# msp430.net
KiCad netlist of a schematic drawn in Altium Designer
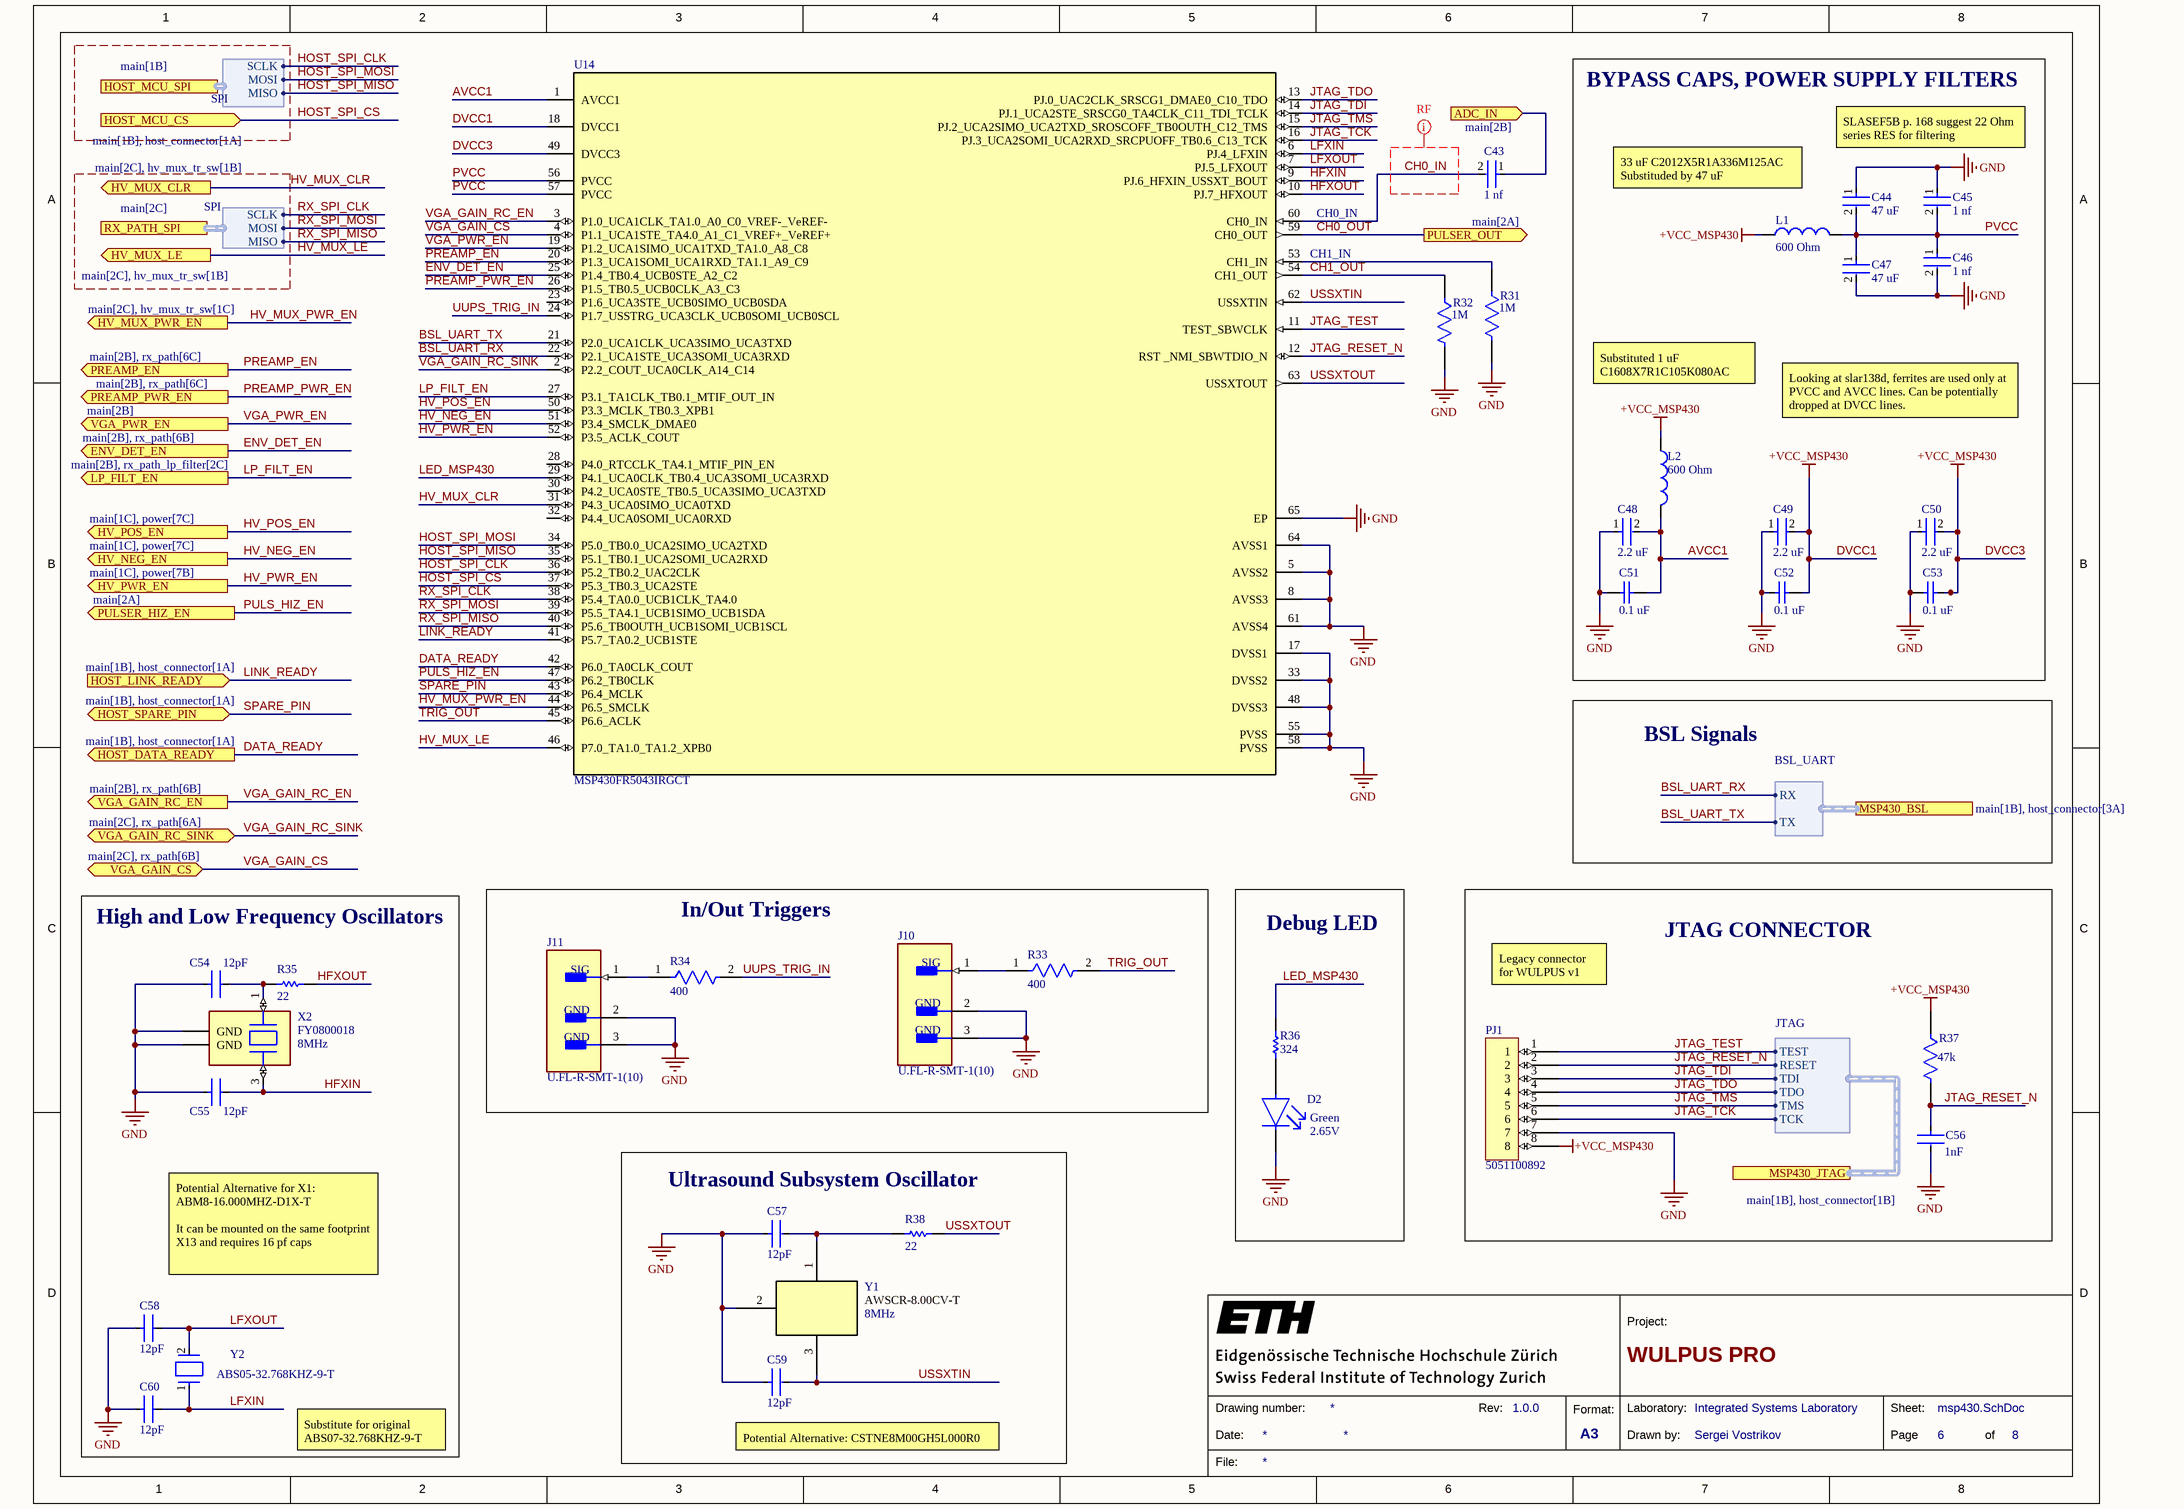
[diagram p0: msp430.SchDoc]

(export (version "E")
  (design (tool "Eeschema 10.0.6"))
  (components
    (comp (ref "C43")
      (value "1 nf")
      (footprint "FP-GRM155-0_05-IPC_B")
      (description "GRM1555C1H102JA01D")
      (fields (field (name "TOLERANCE") "5%") (field (name "VOLTAGE") "50V"))
      (libsource (lib "") (part "02cd4be3c70576c341d710602a673aa_1"))
    )
    (comp (ref "C44")
      (value "47 uF")
      (footprint "FP-GRM188-0_2-MFG")
      (description "GRM188R60J476ME01D")
      (fields (field (name "TOLERANCE") "20%"))
      (libsource (lib "Altium Content Vault") (part "b4654b650e69147ec39a6b967a45e02"))
    )
    (comp (ref "C45")
      (value "1 nf")
      (footprint "FP-GRM155-0_05-IPC_B")
      (description "GRM1555C1H102JA01D")
      (fields (field (name "TOLERANCE") "5%") (field (name "VOLTAGE") "50V"))
      (libsource (lib "") (part "02cd4be3c70576c341d710602a673aa_1"))
    )
    (comp (ref "C46")
      (value "1 nf")
      (footprint "FP-GRM155-0_05-IPC_B")
      (description "GRM1555C1H102JA01D")
      (fields (field (name "TOLERANCE") "5%") (field (name "VOLTAGE") "50V"))
      (libsource (lib "") (part "02cd4be3c70576c341d710602a673aa_1"))
    )
    (comp (ref "C47")
      (value "47 uF")
      (footprint "FP-GRM188-0_2-MFG")
      (description "GRM188R60J476ME01D")
      (fields (field (name "TOLERANCE") "20%"))
      (libsource (lib "Altium Content Vault") (part "b4654b650e69147ec39a6b967a45e02"))
    )
    (comp (ref "C48")
      (value "2.2 uF")
      (footprint "FP-C1005-050-0_15-0_1-MFG")
      (description "C1005X7S1A225K050BC")
      (fields (field (name "TOLERANCE") "10%"))
      (libsource (lib "Altium Content Vault") (part "b4654b650e69147ec39a6b967a45e02"))
    )
    (comp (ref "C49")
      (value "2.2 uF")
      (footprint "FP-C1005-050-0_15-0_1-MFG")
      (description "C1005X7S1A225K050BC")
      (fields (field (name "TOLERANCE") "10%"))
      (libsource (lib "Altium Content Vault") (part "b4654b650e69147ec39a6b967a45e02"))
    )
    (comp (ref "C50")
      (value "2.2 uF")
      (footprint "FP-C1005-050-0_15-0_1-MFG")
      (description "C1005X7S1A225K050BC")
      (fields (field (name "TOLERANCE") "10%"))
      (libsource (lib "Altium Content Vault") (part "b4654b650e69147ec39a6b967a45e02"))
    )
    (comp (ref "C51")
      (value "0.1 uF")
      (footprint "CAPC1005X55X30LL05T10")
      (description "C0402C104K4RACTU")
      (fields (field (name "MANUFACTURER") "Kemet"))
      (libsource (lib "Altium Content Vault") (part "CAP"))
    )
    (comp (ref "C52")
      (value "0.1 uF")
      (footprint "CAPC1005X55X30LL05T10")
      (description "C0402C104K4RACTU")
      (fields (field (name "MANUFACTURER") "Kemet"))
      (libsource (lib "Altium Content Vault") (part "CAP"))
    )
    (comp (ref "C53")
      (value "0.1 uF")
      (footprint "CAPC1005X55X30LL05T10")
      (description "C0402C104K4RACTU")
      (fields (field (name "MANUFACTURER") "Kemet"))
      (libsource (lib "Altium Content Vault") (part "CAP"))
    )
    (comp (ref "C54")
      (value "GJM1555C1H120GB01D")
      (footprint "FP-GJM155-0_05-IPC_A")
      (description "Multi-Layer Ceramic Capacitor 12pF C0G  ±2% 0402 Paper T/R")
      (fields (field (name "TOLERANCE") "2%") (field (name "CAPACITANCE") "12pF"))
      (libsource (lib "Altium Content Vault") (part "02cd4be3c70576c341d710602a673aa"))
    )
    (comp (ref "C55")
      (value "GJM1555C1H120GB01D")
      (footprint "FP-GJM155-0_05-IPC_A")
      (description "Multi-Layer Ceramic Capacitor 12pF C0G  ±2% 0402 Paper T/R")
      (fields (field (name "TOLERANCE") "2%") (field (name "CAPACITANCE") "12pF"))
      (libsource (lib "Altium Content Vault") (part "02cd4be3c70576c341d710602a673aa"))
    )
    (comp (ref "C56")
      (value "GRM1555C1H102JA01D")
      (footprint "FP-GRM155-0_05-IPC_B")
      (description "Chip Multilayer Ceramic Capacitors for General Purpose, 0402, 1000pF, C0G, 30ppm/°C, 5%, 50V")
      (fields
        (field (name "TOLERANCE") "5%")
        (field (name "VOLTAGE") "50V")
        (field (name "CAPACITANCE") "1nF")
      )
      (libsource (lib "Altium Content Vault") (part "02cd4be3c70576c341d710602a673aa"))
    )
    (comp (ref "C57")
      (value "GJM1555C1H120GB01D")
      (footprint "FP-GJM155-0_05-IPC_A")
      (description "Multi-Layer Ceramic Capacitor 12pF C0G  ±2% 0402 Paper T/R")
      (fields (field (name "TOLERANCE") "2%") (field (name "CAPACITANCE") "12pF"))
      (libsource (lib "Altium Content Vault") (part "02cd4be3c70576c341d710602a673aa"))
    )
    (comp (ref "C58")
      (value "GJM1555C1H120GB01D")
      (footprint "FP-GJM155-0_05-IPC_A")
      (description "Multi-Layer Ceramic Capacitor 12pF C0G  ±2% 0402 Paper T/R")
      (fields (field (name "TOLERANCE") "2%") (field (name "CAPACITANCE") "12pF"))
      (libsource (lib "Altium Content Vault") (part "02cd4be3c70576c341d710602a673aa"))
    )
    (comp (ref "C59")
      (value "GJM1555C1H120GB01D")
      (footprint "FP-GJM155-0_05-IPC_A")
      (description "Multi-Layer Ceramic Capacitor 12pF C0G  ±2% 0402 Paper T/R")
      (fields (field (name "TOLERANCE") "2%") (field (name "CAPACITANCE") "12pF"))
      (libsource (lib "Altium Content Vault") (part "02cd4be3c70576c341d710602a673aa"))
    )
    (comp (ref "C60")
      (value "GJM1555C1H120GB01D")
      (footprint "FP-GJM155-0_05-IPC_A")
      (description "Multi-Layer Ceramic Capacitor 12pF C0G  ±2% 0402 Paper T/R")
      (fields (field (name "TOLERANCE") "2%") (field (name "CAPACITANCE") "12pF"))
      (libsource (lib "Altium Content Vault") (part "02cd4be3c70576c341d710602a673aa"))
    )
    (comp (ref "D2")
      (value "APHD1608LZGCK")
      (footprint "FP-APHD1608LZGCK-MFG")
      (description "LED GREEN CLEAR 1608 SMD")
      (fields (field (name "FORWARD VOLTAGE") "2.65V") (field (name "COLOR") "Green"))
      (libsource (lib "Altium Content Vault") (part "8706943c75ba83719d021d2fdc84c58"))
    )
    (comp (ref "J10")
      (value "U.FL-R-SMT-1(10)")
      (footprint "FP-U_FL-R-SMT-1_10-MFG")
      (description "CONN U.FL RCPT STR 50 OHM SMD")
      (libsource (lib "Altium Content Vault") (part "7158abf7d987fa84906f6fb0d115710"))
    )
    (comp (ref "J11")
      (value "U.FL-R-SMT-1(10)")
      (footprint "FP-U_FL-R-SMT-1_10-MFG")
      (description "CONN U.FL RCPT STR 50 OHM SMD")
      (libsource (lib "Altium Content Vault") (part "7158abf7d987fa84906f6fb0d115710"))
    )
    (comp (ref "L1")
      (value "742792040")
      (footprint "SMD-0805")
      (description "SMD EMI Suppression Ferrite Bead WE-CBF, Z = 600 Ohm")
      (fields (field (name "IMPEDANCE") "600 Ohm"))
      (libsource (lib "Altium Content Vault") (part "PAS-IND-INDUCTOR-2"))
    )
    (comp (ref "L2")
      (value "742792040")
      (footprint "SMD-0805")
      (description "SMD EMI Suppression Ferrite Bead WE-CBF, Z = 600 Ohm")
      (fields (field (name "IMPEDANCE") "600 Ohm"))
      (libsource (lib "Altium Content Vault") (part "PAS-IND-INDUCTOR-2"))
    )
    (comp (ref "PJ1")
      (value "5051100892")
      (footprint "MOLEX_5051100892")
      (libsource (lib "wulpus") (part "MOLEX_5051100892"))
    )
    (comp (ref "R31")
      (value "CRCW04021M00FKED")
      (footprint "FP-CRCW0402-e3-MFG")
      (description "RES Thick Film, 1MΩ, 1%, 0.063W, 100ppm/°C, 0402")
      (fields (field (name "TOLERANCE") "1%") (field (name "RESISTANCE") "1M"))
      (libsource (lib "Altium Content Vault") (part "1029c3af85768c4190bb7ad29bc67b5"))
    )
    (comp (ref "R32")
      (value "CRCW04021M00FKED")
      (footprint "FP-CRCW0402-e3-MFG")
      (description "RES Thick Film, 1MΩ, 1%, 0.063W, 100ppm/°C, 0402")
      (fields (field (name "TOLERANCE") "1%") (field (name "RESISTANCE") "1M"))
      (libsource (lib "Altium Content Vault") (part "1029c3af85768c4190bb7ad29bc67b5"))
    )
    (comp (ref "R33")
      (value "400")
      (footprint "FP-CRCW0402-C-e3-MFG")
      (description "CRCW04021R00FKEDC")
      (fields (field (name "TOLERANCE") "1%"))
      (libsource (lib "") (part "1029c3af85768c4190bb7ad29bc67b5_1"))
    )
    (comp (ref "R34")
      (value "400")
      (footprint "FP-CRCW0402-C-e3-MFG")
      (description "CRCW04021R00FKEDC")
      (fields (field (name "TOLERANCE") "1%"))
      (libsource (lib "") (part "1029c3af85768c4190bb7ad29bc67b5_1"))
    )
    (comp (ref "R35")
      (value "RC0402JR-0722RL")
      (footprint "RESC1005X40X25NL05T10")
      (fields (field (name "MANUFACTURER") "Yageo / Phycomp") (field (name "RESISTANCE") "22"))
      (libsource (lib "Altium Content Vault") (part "RES"))
    )
    (comp (ref "R36")
      (value "CPF0402B324RE1")
      (footprint "RESC1005X35X20ML05T10")
      (fields (field (name "MANUFACTURER") "TE Connectivity / AMP") (field (name "RESISTANCE") "324"))
      (libsource (lib "Altium Content Vault") (part "RES"))
    )
    (comp (ref "R37")
      (value "CRCW040247K0FKED")
      (footprint "FP-CRCW0402-e3-IPC_C")
      (description "RES Thick Film, 47kΩ, 1%, 0.063W, 100ppm/°C, 0402")
      (fields (field (name "TOLERANCE") "1%") (field (name "RESISTANCE") "47k"))
      (libsource (lib "Altium Content Vault") (part "1029c3af85768c4190bb7ad29bc67b5"))
    )
    (comp (ref "R38")
      (value "RC0402JR-0722RL")
      (footprint "RESC1005X40X25NL05T10")
      (fields (field (name "MANUFACTURER") "Yageo / Phycomp") (field (name "RESISTANCE") "22"))
      (libsource (lib "Altium Content Vault") (part "RES"))
    )
    (comp (ref "U14")
      (value "MSP430FR5043IRGCT")
      (footprint "RGC0064G")
      (description "No Description Available")
      (fields (field (name "COPYRIGHT") "Copyright (C) 2021 Ultra Librarian. All rights reserved."))
      (libsource (lib "Schlib1") (part "MSP430FR5043IRGCT"))
    )
    (comp (ref "X2")
      (value "FY0800018")
      (footprint "XTAL_ECS-80-18-30B-AGN-TR")
      (description "Crystal 8MHz ±30ppm (Tol) ±30ppm (Stability) 18pF FUND 100Ohm 4-Pin SMD T/R")
      (fields (field (name "MANUFACTURER") "Diodes") (field (name "FREQUENCY") "8MHz"))
      (libsource (lib "Schlib1") (part "FY0800018"))
    )
    (comp (ref "Y1")
      (value "AWSCR-8.00CV-T")
      (footprint "AWSCR-8.00CV-T_ABR")
      (description "No Description Available")
      (fields
        (field (name "MANUFACTURER_PART_NUMBER") "AWSCR-8.00CV-T")
        (field (name "FREQUENCY") "8MHz")
        (field (name "COPYRIGHT") "Copyright (C) 2021 Ultra Librarian. All rights reserved.")
      )
      (libsource (lib "Schlib1") (part "AWSCR-8.00CV-T"))
    )
    (comp (ref "Y2")
      (value "ABS05-32.768KHZ-9-T")
      (footprint "FP-ABS05-MFG")
      (description "CRYSTAL 32.7680KHZ 9PF SMD")
      (fields (field (name "TOLERANCE") "20ppm"))
      (libsource (lib "Altium Content Vault") (part "c23a69dc6c9e2f18f2079038eb95dd1"))
    )
  )
  (nets
    (net (code "4") (name "+VCC_MSP430") (class "Default")
      (node (ref "C49") (pin "2") (pinfunction "2_2") (pintype "passive"))
      (node (ref "C50") (pin "2") (pinfunction "2_2") (pintype "passive"))
      (node (ref "C52") (pin "1") (pinfunction "1_1") (pintype "passive"))
      (node (ref "C53") (pin "1") (pinfunction "1_1") (pintype "passive"))
      (node (ref "L1") (pin "1") (pinfunction "1_1") (pintype "passive"))
      (node (ref "L2") (pin "1") (pinfunction "1_1") (pintype "passive"))
      (node (ref "PJ1") (pin "8") (pinfunction "8_8") (pintype "bidirectional"))
      (node (ref "R37") (pin "1") (pinfunction "1_1") (pintype "passive"))
      (node (ref "U14") (pin "18") (pinfunction "DVCC1_18") (pintype "power_in"))
      (node (ref "U14") (pin "49") (pinfunction "DVCC3_49") (pintype "power_in"))
    )
    (net (code "5") (name "/ADC_IN") (class "Default")
      (node (ref "C43") (pin "1") (pinfunction "1_1") (pintype "passive"))
    )
    (net (code "6") (name "/AVCC1") (class "Default")
      (node (ref "C48") (pin "2") (pinfunction "2_2") (pintype "passive"))
      (node (ref "C51") (pin "1") (pinfunction "1_1") (pintype "passive"))
      (node (ref "L2") (pin "2") (pinfunction "2_2") (pintype "passive"))
      (node (ref "U14") (pin "1") (pinfunction "AVCC1_1") (pintype "power_in"))
    )
    (net (code "7") (name "/BSL_UART_RX") (class "Default")
      (node (ref "U14") (pin "22") (pinfunction "P2.1_UCA1STE_UCA3SOMI_UCA3RXD_22") (pintype "bidirectional"))
    )
    (net (code "8") (name "/BSL_UART_TX") (class "Default")
      (node (ref "U14") (pin "21") (pinfunction "P2.0_UCA1CLK_UCA3SIMO_UCA3TXD_21") (pintype "bidirectional"))
    )
    (net (code "9") (name "/CH0_IN") (class "Default")
      (node (ref "C43") (pin "2") (pinfunction "2_2") (pintype "passive"))
      (node (ref "U14") (pin "60") (pinfunction "CH0_IN_60") (pintype "input"))
    )
    (net (code "10") (name "/CH0_OUT") (class "Default")
      (node (ref "U14") (pin "59") (pinfunction "CH0_OUT_59") (pintype "output"))
    )
    (net (code "11") (name "/CH1_OUT") (class "Default")
      (node (ref "R32") (pin "1") (pinfunction "1_1") (pintype "passive"))
      (node (ref "U14") (pin "54") (pinfunction "CH1_OUT_54") (pintype "output"))
    )
    (net (code "12") (name "/DATA_READY") (class "Default")
      (node (ref "U14") (pin "42") (pinfunction "P6.0_TA0CLK_COUT_42") (pintype "bidirectional"))
    )
    (net (code "13") (name "/ENV_DET_EN") (class "Default")
      (node (ref "U14") (pin "25") (pinfunction "P1.4_TB0.4_UCB0STE_A2_C2_25") (pintype "bidirectional"))
    )
    (net (code "14") (name "/HFXIN") (class "Default")
      (node (ref "C55") (pin "2") (pinfunction "2_2") (pintype "passive"))
      (node (ref "U14") (pin "9") (pinfunction "PJ.6_HFXIN_USSXT_BOUT_9") (pintype "bidirectional"))
      (node (ref "X2") (pin "3") (pinfunction "OUT/IN_3") (pintype "bidirectional"))
    )
    (net (code "15") (name "/HFXOUT") (class "Default")
      (node (ref "R35") (pin "2") (pinfunction "2_2") (pintype "passive"))
      (node (ref "U14") (pin "10") (pinfunction "PJ.7_HFXOUT_10") (pintype "bidirectional"))
    )
    (net (code "16") (name "/HOST_SPI_CLK") (class "Default")
      (node (ref "U14") (pin "36") (pinfunction "P5.2_TB0.2_UAC2CLK_36") (pintype "bidirectional"))
    )
    (net (code "17") (name "/HOST_SPI_CS") (class "Default")
      (node (ref "U14") (pin "37") (pinfunction "P5.3_TB0.3_UCA2STE_37") (pintype "bidirectional"))
    )
    (net (code "18") (name "/HOST_SPI_MISO") (class "Default")
      (node (ref "U14") (pin "35") (pinfunction "P5.1_TB0.1_UCA2SOMI_UCA2RXD_35") (pintype "bidirectional"))
    )
    (net (code "19") (name "/HOST_SPI_MOSI") (class "Default")
      (node (ref "U14") (pin "34") (pinfunction "P5.0_TB0.0_UCA2SIMO_UCA2TXD_34") (pintype "bidirectional"))
    )
    (net (code "20") (name "/HV_MUX_CLR") (class "Default")
      (node (ref "U14") (pin "31") (pinfunction "P4.3_UCA0SIMO_UCA0TXD_31") (pintype "bidirectional"))
    )
    (net (code "21") (name "/HV_MUX_LE") (class "Default")
      (node (ref "U14") (pin "46") (pinfunction "P7.0_TA1.0_TA1.2_XPB0_46") (pintype "bidirectional"))
    )
    (net (code "22") (name "/HV_MUX_PWR_EN") (class "Default")
      (node (ref "U14") (pin "44") (pinfunction "P6.5_SMCLK_44") (pintype "bidirectional"))
    )
    (net (code "23") (name "/HV_NEG_EN") (class "Default")
      (node (ref "U14") (pin "51") (pinfunction "P3.4_SMCLK_DMAE0_51") (pintype "bidirectional"))
    )
    (net (code "24") (name "/HV_POS_EN") (class "Default")
      (node (ref "U14") (pin "50") (pinfunction "P3.3_MCLK_TB0.3_XPB1_50") (pintype "bidirectional"))
    )
    (net (code "25") (name "/HV_PWR_EN") (class "Default")
      (node (ref "U14") (pin "52") (pinfunction "P3.5_ACLK_COUT_52") (pintype "bidirectional"))
    )
    (net (code "26") (name "/JTAG_RESET_N") (class "Default")
      (node (ref "C56") (pin "1") (pinfunction "1_1") (pintype "passive"))
      (node (ref "PJ1") (pin "2") (pinfunction "2_2") (pintype "bidirectional"))
      (node (ref "R37") (pin "2") (pinfunction "2_2") (pintype "passive"))
      (node (ref "U14") (pin "12") (pinfunction "RST__NMI_SBWTDIO_N_12") (pintype "bidirectional"))
    )
    (net (code "27") (name "/JTAG_TCK") (class "Default")
      (node (ref "PJ1") (pin "6") (pinfunction "6_6") (pintype "bidirectional"))
      (node (ref "U14") (pin "16") (pinfunction "PJ.3_UCA2SOMI_UCA2RXD_SRCPUOFF_TB0.6_C13_TCK_16") (pintype "bidirectional"))
    )
    (net (code "28") (name "/JTAG_TDI") (class "Default")
      (node (ref "PJ1") (pin "3") (pinfunction "3_3") (pintype "bidirectional"))
      (node (ref "U14") (pin "14") (pinfunction "PJ.1_UCA2STE_SRSCG0_TA4CLK_C11_TDI_TCLK_14") (pintype "bidirectional"))
    )
    (net (code "29") (name "/JTAG_TDO") (class "Default")
      (node (ref "PJ1") (pin "4") (pinfunction "4_4") (pintype "bidirectional"))
      (node (ref "U14") (pin "13") (pinfunction "PJ.0_UAC2CLK_SRSCG1_DMAE0_C10_TDO_13") (pintype "bidirectional"))
    )
    (net (code "30") (name "/JTAG_TEST") (class "Default")
      (node (ref "PJ1") (pin "1") (pinfunction "1_1") (pintype "bidirectional"))
      (node (ref "U14") (pin "11") (pinfunction "TEST_SBWCLK_11") (pintype "input"))
    )
    (net (code "31") (name "/JTAG_TMS") (class "Default")
      (node (ref "PJ1") (pin "5") (pinfunction "5_5") (pintype "bidirectional"))
      (node (ref "U14") (pin "15") (pinfunction "PJ.2_UCA2SIMO_UCA2TXD_SROSCOFF_TB0OUTH_C12_TMS_15") (pintype "bidirectional"))
    )
    (net (code "32") (name "/LED_MSP430") (class "Default")
      (node (ref "R36") (pin "1") (pinfunction "1_1") (pintype "passive"))
      (node (ref "U14") (pin "29") (pinfunction "P4.1_UCA0CLK_TB0.4_UCA3SOMI_UCA3RXD_29") (pintype "bidirectional"))
    )
    (net (code "33") (name "/LFXIN") (class "Default")
      (node (ref "C60") (pin "2") (pinfunction "2_2") (pintype "passive"))
      (node (ref "U14") (pin "6") (pinfunction "PJ.4_LFXIN_6") (pintype "bidirectional"))
      (node (ref "Y2") (pin "1") (pinfunction "1_1") (pintype "passive"))
    )
    (net (code "34") (name "/LFXOUT") (class "Default")
      (node (ref "C58") (pin "2") (pinfunction "2_2") (pintype "passive"))
      (node (ref "U14") (pin "7") (pinfunction "PJ.5_LFXOUT_7") (pintype "bidirectional"))
      (node (ref "Y2") (pin "2") (pinfunction "2_2") (pintype "passive"))
    )
    (net (code "35") (name "/LINK_READY") (class "Default")
      (node (ref "U14") (pin "41") (pinfunction "P5.7_TA0.2_UCB1STE_41") (pintype "bidirectional"))
    )
    (net (code "36") (name "/LP_FILT_EN") (class "Default")
      (node (ref "U14") (pin "27") (pinfunction "P3.1_TA1CLK_TB0.1_MTIF_OUT_IN_27") (pintype "bidirectional"))
    )
    (net (code "37") (name "/PREAMP_EN") (class "Default")
      (node (ref "U14") (pin "20") (pinfunction "P1.3_UCA1SOMI_UCA1RXD_TA1.1_A9_C9_20") (pintype "bidirectional"))
    )
    (net (code "38") (name "/PREAMP_PWR_EN") (class "Default")
      (node (ref "U14") (pin "26") (pinfunction "P1.5_TB0.5_UCB0CLK_A3_C3_26") (pintype "bidirectional"))
    )
    (net (code "39") (name "/PULS_HIZ_EN") (class "Default")
      (node (ref "U14") (pin "47") (pinfunction "P6.2_TB0CLK_47") (pintype "bidirectional"))
    )
    (net (code "40") (name "/PVCC") (class "Default")
      (node (ref "C44") (pin "2") (pinfunction "2_2") (pintype "passive"))
      (node (ref "C45") (pin "2") (pinfunction "2_2") (pintype "passive"))
      (node (ref "C46") (pin "1") (pinfunction "1_1") (pintype "passive"))
      (node (ref "C47") (pin "1") (pinfunction "1_1") (pintype "passive"))
      (node (ref "L1") (pin "2") (pinfunction "2_2") (pintype "passive"))
      (node (ref "U14") (pin "56") (pinfunction "PVCC_56") (pintype "power_in"))
      (node (ref "U14") (pin "57") (pinfunction "PVCC_57") (pintype "power_in"))
    )
    (net (code "41") (name "/RX_SPI_CLK") (class "Default")
      (node (ref "U14") (pin "38") (pinfunction "P5.4_TA0.0_UCB1CLK_TA4.0_38") (pintype "bidirectional"))
    )
    (net (code "42") (name "/RX_SPI_MISO") (class "Default")
      (node (ref "U14") (pin "40") (pinfunction "P5.6_TB0OUTH_UCB1SOMI_UCB1SCL_40") (pintype "bidirectional"))
    )
    (net (code "43") (name "/RX_SPI_MOSI") (class "Default")
      (node (ref "U14") (pin "39") (pinfunction "P5.5_TA4.1_UCB1SIMO_UCB1SDA_39") (pintype "bidirectional"))
    )
    (net (code "44") (name "/SPARE_PIN") (class "Default")
      (node (ref "U14") (pin "43") (pinfunction "P6.4_MCLK_43") (pintype "bidirectional"))
    )
    (net (code "45") (name "/TRIG_OUT") (class "Default")
      (node (ref "R33") (pin "2") (pinfunction "2_2") (pintype "passive"))
      (node (ref "U14") (pin "45") (pinfunction "P6.6_ACLK_45") (pintype "bidirectional"))
    )
    (net (code "46") (name "/USSXTIN") (class "Default")
      (node (ref "C59") (pin "2") (pinfunction "2_2") (pintype "passive"))
      (node (ref "U14") (pin "62") (pinfunction "USSXTIN_62") (pintype "input"))
      (node (ref "Y1") (pin "3") (pinfunction "3_3") (pintype "passive"))
    )
    (net (code "47") (name "/USSXTOUT") (class "Default")
      (node (ref "R38") (pin "2") (pinfunction "2_2") (pintype "passive"))
      (node (ref "U14") (pin "63") (pinfunction "USSXTOUT_63") (pintype "output"))
    )
    (net (code "48") (name "/UUPS_TRIG_IN") (class "Default")
      (node (ref "R34") (pin "2") (pinfunction "2_2") (pintype "passive"))
      (node (ref "U14") (pin "24") (pinfunction "P1.7_USSTRG_UCA3CLK_UCB0SOMI_UCB0SCL_24") (pintype "bidirectional"))
    )
    (net (code "49") (name "/VGA_GAIN_CS") (class "Default")
      (node (ref "U14") (pin "4") (pinfunction "P1.1_UCA1STE_TA4.0_A1_C1_VREF+_VeREF+_4") (pintype "bidirectional"))
    )
    (net (code "50") (name "/VGA_GAIN_RC_EN") (class "Default")
      (node (ref "U14") (pin "3") (pinfunction "P1.0_UCA1CLK_TA1.0_A0_C0_VREF-_VeREF-_3") (pintype "bidirectional"))
    )
    (net (code "51") (name "/VGA_GAIN_RC_SINK") (class "Default")
      (node (ref "U14") (pin "2") (pinfunction "P2.2_COUT_UCA0CLK_A14_C14_2") (pintype "bidirectional"))
    )
    (net (code "52") (name "/VGA_PWR_EN") (class "Default")
      (node (ref "U14") (pin "19") (pinfunction "P1.2_UCA1SIMO_UCA1TXD_TA1.0_A8_C8_19") (pintype "bidirectional"))
    )
    (net (code "56") (name "GND") (class "Default")
      (node (ref "C44") (pin "1") (pinfunction "1_1") (pintype "passive"))
      (node (ref "C45") (pin "1") (pinfunction "1_1") (pintype "passive"))
      (node (ref "C46") (pin "2") (pinfunction "2_2") (pintype "passive"))
      (node (ref "C47") (pin "2") (pinfunction "2_2") (pintype "passive"))
      (node (ref "C48") (pin "1") (pinfunction "1_1") (pintype "passive"))
      (node (ref "C49") (pin "1") (pinfunction "1_1") (pintype "passive"))
      (node (ref "C50") (pin "1") (pinfunction "1_1") (pintype "passive"))
      (node (ref "C51") (pin "2") (pinfunction "2_2") (pintype "passive"))
      (node (ref "C52") (pin "2") (pinfunction "2_2") (pintype "passive"))
      (node (ref "C53") (pin "2") (pinfunction "2_2") (pintype "passive"))
      (node (ref "C54") (pin "1") (pinfunction "1_1") (pintype "passive"))
      (node (ref "C55") (pin "1") (pinfunction "1_1") (pintype "passive"))
      (node (ref "C56") (pin "2") (pinfunction "2_2") (pintype "passive"))
      (node (ref "C57") (pin "1") (pinfunction "1_1") (pintype "passive"))
      (node (ref "C58") (pin "1") (pinfunction "1_1") (pintype "passive"))
      (node (ref "C59") (pin "1") (pinfunction "1_1") (pintype "passive"))
      (node (ref "C60") (pin "1") (pinfunction "1_1") (pintype "passive"))
      (node (ref "D2") (pin "1") (pinfunction "C_1") (pintype "passive"))
      (node (ref "J10") (pin "2") (pinfunction "GND_2") (pintype "power_in"))
      (node (ref "J10") (pin "3") (pinfunction "GND_3") (pintype "power_in"))
      (node (ref "J11") (pin "2") (pinfunction "GND_2") (pintype "power_in"))
      (node (ref "J11") (pin "3") (pinfunction "GND_3") (pintype "power_in"))
      (node (ref "PJ1") (pin "7") (pinfunction "7_7") (pintype "bidirectional"))
      (node (ref "R31") (pin "2") (pinfunction "2_2") (pintype "passive"))
      (node (ref "R32") (pin "2") (pinfunction "2_2") (pintype "passive"))
      (node (ref "U14") (pin "17") (pinfunction "DVSS1_17") (pintype "power_in"))
      (node (ref "U14") (pin "33") (pinfunction "DVSS2_33") (pintype "power_in"))
      (node (ref "U14") (pin "48") (pinfunction "DVSS3_48") (pintype "power_in"))
      (node (ref "U14") (pin "5") (pinfunction "AVSS2_5") (pintype "power_in"))
      (node (ref "U14") (pin "55") (pinfunction "PVSS_55") (pintype "power_in"))
      (node (ref "U14") (pin "58") (pinfunction "PVSS_58") (pintype "power_in"))
      (node (ref "U14") (pin "61") (pinfunction "AVSS4_61") (pintype "power_in"))
      (node (ref "U14") (pin "64") (pinfunction "AVSS1_64") (pintype "power_in"))
      (node (ref "U14") (pin "65") (pinfunction "EP_65") (pintype "passive"))
      (node (ref "U14") (pin "8") (pinfunction "AVSS3_8") (pintype "power_in"))
      (node (ref "X2") (pin "2") (pinfunction "GND_2") (pintype "power_in"))
      (node (ref "X2") (pin "4") (pinfunction "GND_4") (pintype "power_in"))
      (node (ref "Y1") (pin "2") (pinfunction "2_2") (pintype "passive"))
    )
    (net (code "57") (name "Net-(C57-Pad2)") (class "Default")
      (node (ref "C57") (pin "2") (pinfunction "2_2") (pintype "passive"))
      (node (ref "R38") (pin "1") (pinfunction "1_1") (pintype "passive"))
      (node (ref "Y1") (pin "1") (pinfunction "1_1") (pintype "passive"))
    )
    (net (code "58") (name "Net-(D2-A)") (class "Default")
      (node (ref "D2") (pin "2") (pinfunction "A_2") (pintype "passive"))
      (node (ref "R36") (pin "2") (pinfunction "2_2") (pintype "passive"))
    )
    (net (code "59") (name "Net-(J10-SIG)") (class "Default")
      (node (ref "J10") (pin "1") (pinfunction "SIG_1") (pintype "input"))
      (node (ref "R33") (pin "1") (pinfunction "1_1") (pintype "passive"))
    )
    (net (code "60") (name "Net-(J11-SIG)") (class "Default")
      (node (ref "J11") (pin "1") (pinfunction "SIG_1") (pintype "input"))
      (node (ref "R34") (pin "1") (pinfunction "1_1") (pintype "passive"))
    )
    (net (code "61") (name "Net-(U14-CH1_IN)") (class "Default")
      (node (ref "R31") (pin "1") (pinfunction "1_1") (pintype "passive"))
      (node (ref "U14") (pin "53") (pinfunction "CH1_IN_53") (pintype "input"))
    )
    (net (code "62") (name "Net-(X2-IN{slash}OUT)") (class "Default")
      (node (ref "C54") (pin "2") (pinfunction "2_2") (pintype "passive"))
      (node (ref "R35") (pin "1") (pinfunction "1_1") (pintype "passive"))
      (node (ref "X2") (pin "1") (pinfunction "IN/OUT_1") (pintype "bidirectional"))
    )
    (net (code "63") (name "unconnected-(U14-P1.6_UCA3STE_UCB0SIMO_UCB0SDA-Pad23)") (class "Default")
      (node (ref "U14") (pin "23") (pinfunction "P1.6_UCA3STE_UCB0SIMO_UCB0SDA_23") (pintype "bidirectional"))
    )
    (net (code "64") (name "unconnected-(U14-P4.0_RTCCLK_TA4.1_MTIF_PIN_EN-Pad28)") (class "Default")
      (node (ref "U14") (pin "28") (pinfunction "P4.0_RTCCLK_TA4.1_MTIF_PIN_EN_28") (pintype "bidirectional"))
    )
    (net (code "65") (name "unconnected-(U14-P4.2_UCA0STE_TB0.5_UCA3SIMO_UCA3TXD-Pad30)") (class "Default")
      (node (ref "U14") (pin "30") (pinfunction "P4.2_UCA0STE_TB0.5_UCA3SIMO_UCA3TXD_30") (pintype "bidirectional"))
    )
    (net (code "66") (name "unconnected-(U14-P4.4_UCA0SOMI_UCA0RXD-Pad32)") (class "Default")
      (node (ref "U14") (pin "32") (pinfunction "P4.4_UCA0SOMI_UCA0RXD_32") (pintype "bidirectional"))
    )
  )
)
